# LMR12006.net
KiCad netlist of a schematic drawn in Altium Designer
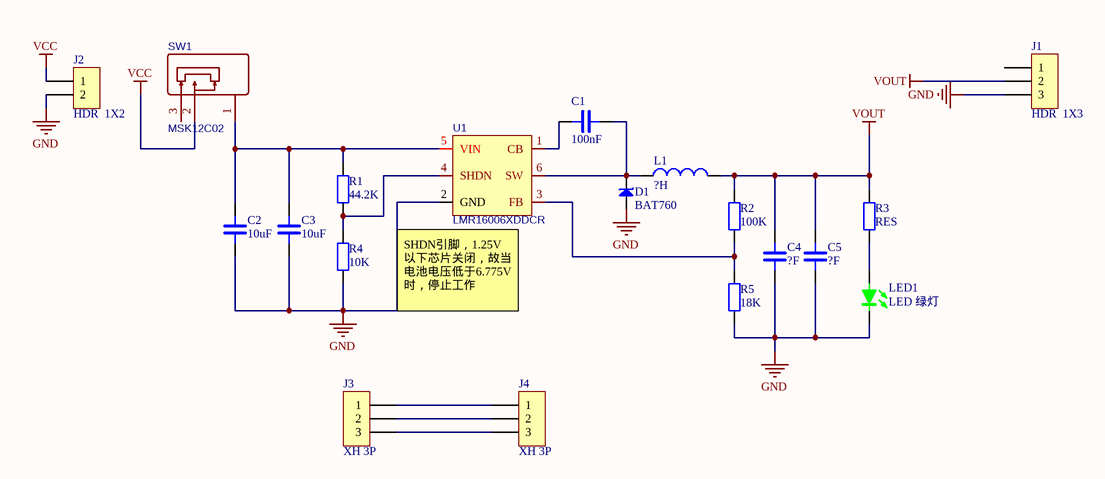
[diagram p0: LMR12006.SchDoc]

(export (version "E")
  (design (tool "Eeschema 10.0.6"))
  (components
    (comp (ref "C1")
      (value "100nF")
      (footprint "C 0603")
      (description "Capacitor")
      (libsource (lib "General") (part "CAP"))
    )
    (comp (ref "C2")
      (value "10uF")
      (footprint "C 1206")
      (description "Capacitor")
      (libsource (lib "General") (part "CAP"))
    )
    (comp (ref "C3")
      (value "10uF")
      (footprint "C 1206")
      (description "Capacitor")
      (libsource (lib "General") (part "CAP"))
    )
    (comp (ref "C4")
      (value "?F")
      (footprint "C 1206")
      (description "Capacitor")
      (libsource (lib "General") (part "CAP"))
    )
    (comp (ref "C5")
      (value "?F")
      (footprint "C 1206")
      (description "Capacitor")
      (libsource (lib "General") (part "CAP"))
    )
    (comp (ref "D1")
      (value "BAT760")
      (footprint "SOD-323")
      (description "肖特基二极管")
      (libsource (lib "General") (part "BAT760"))
    )
    (comp (ref "J1")
      (value "HDR  1X3")
      (footprint "HDR2.54 D-L-F-1X3P")
      (description "Connector")
      (libsource (lib "General") (part "HDR  1X3"))
    )
    (comp (ref "J2")
      (value "HDR  1X2")
      (footprint "HDR2.54 D-L-F-1X2P")
      (description "Connector")
      (libsource (lib "General") (part "HDR  1X2"))
    )
    (comp (ref "J3")
      (value "XH 3P")
      (footprint "XH2.54-3P")
      (description "Connector")
      (libsource (lib "General") (part "XH 3P"))
    )
    (comp (ref "J4")
      (value "XH 3P")
      (footprint "XH2.54-3P")
      (description "Connector")
      (libsource (lib "") (part "XH 3P_1"))
    )
    (comp (ref "L1")
      (value "?H")
      (footprint "SMD 7*7*4")
      (description "Inductor")
      (fields (field (name "PUBLISHER") "Altium Limited"))
      (libsource (lib "General") (part "Inductor"))
    )
    (comp (ref "LED1")
      (value "LED 绿灯")
      (footprint "LED 0603-G")
      (description "LED")
      (libsource (lib "General") (part "LED 绿灯"))
    )
    (comp (ref "R1")
      (value "44.2K")
      (footprint "R 0603")
      (description "Resistor")
      (libsource (lib "General") (part "RES"))
    )
    (comp (ref "R2")
      (value "100K")
      (footprint "R 0603")
      (description "Resistor")
      (libsource (lib "General") (part "RES"))
    )
    (comp (ref "R3")
      (value "RES")
      (footprint "R 0603")
      (description "Resistor")
      (libsource (lib "General") (part "RES"))
    )
    (comp (ref "R4")
      (value "10K")
      (footprint "R 0603")
      (description "Resistor")
      (libsource (lib "General") (part "RES"))
    )
    (comp (ref "R5")
      (value "18K")
      (footprint "R 0603")
      (description "Resistor")
      (libsource (lib "General") (part "RES"))
    )
    (comp (ref "SW1")
      (value "MSK12C02")
      (footprint "*SW-TH_MSK12C02")
      (description "开关")
      (fields (field (name "BOM_SUPPLIER PART") "C431540") (field (name "CONTRIBUTOR") "LCSC"))
      (libsource (lib "General") (part "MSK12C02"))
    )
    (comp (ref "U1")
      (value "LMR16006XDDCR")
      (footprint "SOT23-6")
      (description "DC-DC降压模块")
      (fields (field (name "BOM_SUPPLIER PART") "C87080"))
      (libsource (lib "General") (part "LMR16006XDDCR"))
    )
  )
  (nets
    (net (code "1") (name "GND") (class "Default")
      (node (ref "C2") (pin "2") (pinfunction "2_2") (pintype "passive"))
      (node (ref "C3") (pin "2") (pinfunction "2_2") (pintype "passive"))
      (node (ref "C4") (pin "1") (pinfunction "1_1") (pintype "passive"))
      (node (ref "C5") (pin "1") (pinfunction "1_1") (pintype "passive"))
      (node (ref "D1") (pin "1") (pinfunction "A_1") (pintype "passive"))
      (node (ref "J1") (pin "3") (pinfunction "3_3") (pintype "passive"))
      (node (ref "J2") (pin "2") (pinfunction "2_2") (pintype "passive"))
      (node (ref "LED1") (pin "2") (pinfunction "C_2") (pintype "passive"))
      (node (ref "R4") (pin "1") (pinfunction "1_1") (pintype "passive"))
      (node (ref "R5") (pin "1") (pinfunction "1_1") (pintype "passive"))
      (node (ref "U1") (pin "2") (pinfunction "GND_2") (pintype "passive"))
    )
    (net (code "2") (name "Net-(D1-K)") (class "Default")
      (node (ref "C1") (pin "2") (pinfunction "2_2") (pintype "passive"))
      (node (ref "D1") (pin "2") (pinfunction "K_2") (pintype "passive"))
      (node (ref "L1") (pin "1") (pinfunction "1_1") (pintype "passive"))
      (node (ref "U1") (pin "6") (pinfunction "SW_6") (pintype "passive"))
    )
    (net (code "3") (name "Net-(J3-Pad1)") (class "Default")
      (node (ref "J3") (pin "1") (pinfunction "1_1") (pintype "passive"))
      (node (ref "J4") (pin "1") (pinfunction "1_1") (pintype "passive"))
    )
    (net (code "4") (name "Net-(J3-Pad2)") (class "Default")
      (node (ref "J3") (pin "2") (pinfunction "2_2") (pintype "passive"))
      (node (ref "J4") (pin "2") (pinfunction "2_2") (pintype "passive"))
    )
    (net (code "5") (name "Net-(J3-Pad3)") (class "Default")
      (node (ref "J3") (pin "3") (pinfunction "3_3") (pintype "passive"))
      (node (ref "J4") (pin "3") (pinfunction "3_3") (pintype "passive"))
    )
    (net (code "6") (name "Net-(LED1-A)") (class "Default")
      (node (ref "LED1") (pin "1") (pinfunction "A_1") (pintype "passive"))
      (node (ref "R3") (pin "1") (pinfunction "1_1") (pintype "passive"))
    )
    (net (code "7") (name "Net-(U1-CB)") (class "Default")
      (node (ref "C1") (pin "1") (pinfunction "1_1") (pintype "passive"))
      (node (ref "U1") (pin "1") (pinfunction "CB_1") (pintype "passive"))
    )
    (net (code "8") (name "Net-(U1-FB)") (class "Default")
      (node (ref "R2") (pin "1") (pinfunction "1_1") (pintype "passive"))
      (node (ref "R5") (pin "2") (pinfunction "2_2") (pintype "passive"))
      (node (ref "U1") (pin "3") (pinfunction "FB_3") (pintype "passive"))
    )
    (net (code "9") (name "Net-(U1-SHDN)") (class "Default")
      (node (ref "R1") (pin "1") (pinfunction "1_1") (pintype "passive"))
      (node (ref "R4") (pin "2") (pinfunction "2_2") (pintype "passive"))
      (node (ref "U1") (pin "4") (pinfunction "SHDN_4") (pintype "passive"))
    )
    (net (code "10") (name "Net-(U1-VIN)") (class "Default")
      (node (ref "C2") (pin "1") (pinfunction "1_1") (pintype "passive"))
      (node (ref "C3") (pin "1") (pinfunction "1_1") (pintype "passive"))
      (node (ref "R1") (pin "2") (pinfunction "2_2") (pintype "passive"))
      (node (ref "SW1") (pin "1") (pinfunction "1_1") (pintype "passive"))
      (node (ref "U1") (pin "5") (pinfunction "VIN_5") (pintype "passive"))
    )
    (net (code "11") (name "VCC") (class "Default")
      (node (ref "J2") (pin "1") (pinfunction "1_1") (pintype "passive"))
      (node (ref "SW1") (pin "2") (pinfunction "2_2") (pintype "passive"))
    )
    (net (code "12") (name "VOUT") (class "Default")
      (node (ref "C4") (pin "2") (pinfunction "2_2") (pintype "passive"))
      (node (ref "C5") (pin "2") (pinfunction "2_2") (pintype "passive"))
      (node (ref "J1") (pin "2") (pinfunction "2_2") (pintype "passive"))
      (node (ref "L1") (pin "2") (pinfunction "2_2") (pintype "passive"))
      (node (ref "R2") (pin "2") (pinfunction "2_2") (pintype "passive"))
      (node (ref "R3") (pin "2") (pinfunction "2_2") (pintype "passive"))
    )
    (net (code "13") (name "unconnected-(J1-Pad1)") (class "Default")
      (node (ref "J1") (pin "1") (pinfunction "1_1") (pintype "passive"))
    )
    (net (code "14") (name "unconnected-(SW1-Pad3)") (class "Default")
      (node (ref "SW1") (pin "3") (pinfunction "3_3") (pintype "passive"))
    )
  )
)
